# Mind-Synchronizing-Generator.net
KiCad netlist of a schematic drawn in EAGLE
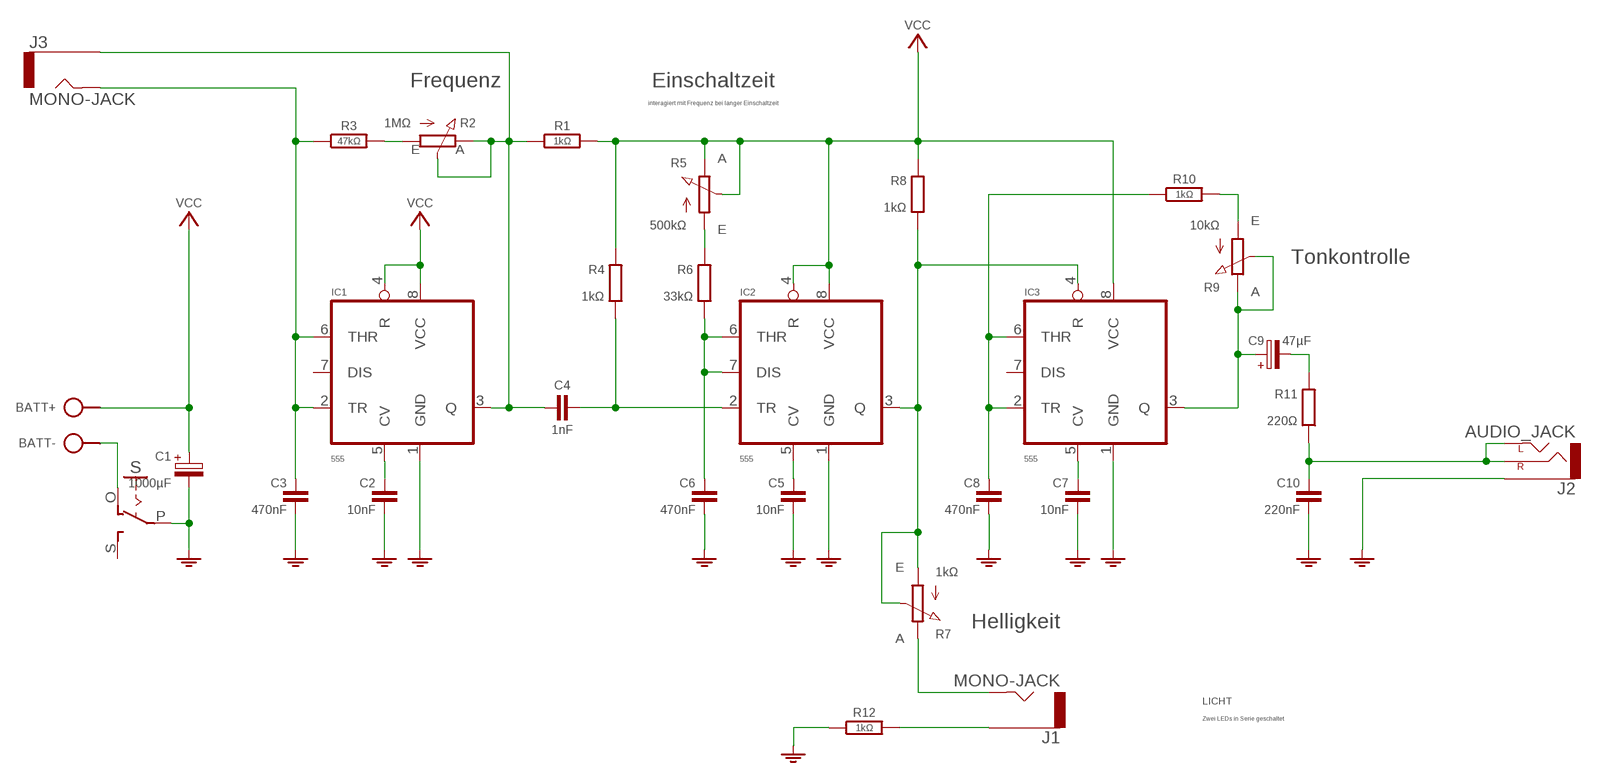
[diagram p0: schematic, sheet 1]

(export (version "E")
  (design (tool "Eeschema 10.0.6"))
  (components
    (comp (ref "BATT")
      (value "SPAD+--+")
      (footprint "eagle-import:SPAD-+")
      (libsource (lib "eagle-import") (part "SPAD+--+"))
    )
    (comp (ref "C1")
      (value "1000µF")
      (footprint "eagle-import:E2,5-6")
      (libsource (lib "eagle-import") (part "CPOLE2.5-6"))
    )
    (comp (ref "C2")
      (value "10nF")
      (footprint "eagle-import:C050-020X044")
      (libsource (lib "eagle-import") (part "C050-020X044"))
    )
    (comp (ref "C3")
      (value "470nF")
      (footprint "eagle-import:C050-040X075")
      (libsource (lib "eagle-import") (part "C050-040X075"))
    )
    (comp (ref "C4")
      (value "1nF")
      (footprint "eagle-import:C050-020X044")
      (libsource (lib "eagle-import") (part "C-H050-020X044"))
    )
    (comp (ref "C5")
      (value "10nF")
      (footprint "eagle-import:C050-020X044_V")
      (libsource (lib "eagle-import") (part "C050-020X044/V"))
    )
    (comp (ref "C6")
      (value "470nF")
      (footprint "eagle-import:C050-040X075")
      (libsource (lib "eagle-import") (part "C050-040X075"))
    )
    (comp (ref "C7")
      (value "10nF")
      (footprint "eagle-import:C075-020X044_V")
      (libsource (lib "eagle-import") (part "C075-020X044/V"))
    )
    (comp (ref "C8")
      (value "470nF")
      (footprint "eagle-import:C050-040X075")
      (libsource (lib "eagle-import") (part "C050-040X075"))
    )
    (comp (ref "C9")
      (value "47µF")
      (footprint "eagle-import:E2,5-4")
      (libsource (lib "eagle-import") (part "CPOL-HE2,5-4"))
    )
    (comp (ref "C10")
      (value "220nF")
      (footprint "eagle-import:C050-025X060")
      (libsource (lib "eagle-import") (part "C025-025X060"))
    )
    (comp (ref "IC1")
      (value "555")
      (footprint "eagle-import:555-DIL")
      (libsource (lib "eagle-import") (part "555_ALT2-LBL"))
    )
    (comp (ref "IC2")
      (value "555")
      (footprint "eagle-import:555-DIL")
      (libsource (lib "eagle-import") (part "555_ALT2-LBL"))
    )
    (comp (ref "IC3")
      (value "555")
      (footprint "eagle-import:555-DIL")
      (libsource (lib "eagle-import") (part "555_ALT2-LBL"))
    )
    (comp (ref "J1")
      (value "MONO-JACK")
      (footprint "eagle-import:STEREOJACK2.5MM_STEREOJACK2.5MM")
      (libsource (lib "eagle-import") (part "MONO-JACK"))
    )
    (comp (ref "J2")
      (value "AUDIO_JACK")
      (footprint "eagle-import:AUDIO-JACK")
      (libsource (lib "eagle-import") (part "AUDIO_JACK"))
    )
    (comp (ref "J3")
      (value "MONO-JACK")
      (footprint "eagle-import:STEREOJACK2.5MM_STEREOJACK2.5MM")
      (libsource (lib "eagle-import") (part "MONO-JACK"))
    )
    (comp (ref "R1")
      (value "1kΩ")
      (footprint "eagle-import:0204_10")
      (libsource (lib "eagle-import") (part "R-H0204/10"))
    )
    (comp (ref "R2")
      (value "1MΩ")
      (footprint "eagle-import:POT-45X40")
      (libsource (lib "eagle-import") (part "POT-H-45X40"))
    )
    (comp (ref "R3")
      (value "47kΩ")
      (footprint "eagle-import:0204_10")
      (libsource (lib "eagle-import") (part "R-H0204/10"))
    )
    (comp (ref "R4")
      (value "1kΩ")
      (footprint "eagle-import:0204_10-V")
      (libsource (lib "eagle-import") (part "R0204/10-V"))
    )
    (comp (ref "R5")
      (value "500kΩ")
      (footprint "eagle-import:POT-45X40")
      (libsource (lib "eagle-import") (part "POT-45X40"))
    )
    (comp (ref "R6")
      (value "33kΩ")
      (footprint "eagle-import:0204_10")
      (libsource (lib "eagle-import") (part "R0204/10"))
    )
    (comp (ref "R7")
      (value "1kΩ")
      (footprint "eagle-import:POT-45X40")
      (libsource (lib "eagle-import") (part "POT-45X40"))
    )
    (comp (ref "R8")
      (value "1kΩ")
      (footprint "eagle-import:0204_10-V")
      (libsource (lib "eagle-import") (part "R0204/10-V"))
    )
    (comp (ref "R9")
      (value "10kΩ")
      (footprint "eagle-import:POT-45X40")
      (libsource (lib "eagle-import") (part "POT-45X40"))
    )
    (comp (ref "R10")
      (value "1kΩ")
      (footprint "eagle-import:0204_10")
      (libsource (lib "eagle-import") (part "R-H0204/10"))
    )
    (comp (ref "R11")
      (value "220Ω")
      (footprint "eagle-import:0204_10-V")
      (libsource (lib "eagle-import") (part "R0204/10-V"))
    )
    (comp (ref "R12")
      (value "1kΩ")
      (footprint "eagle-import:0204_10")
      (libsource (lib "eagle-import") (part "R-H0204/10"))
    )
    (comp (ref "S")
      (value "SL-SW-1P-2T-H")
      (footprint "eagle-import:SLSW-1P2T-H")
      (libsource (lib "eagle-import") (part "SL-SW-1P-2T-H"))
    )
  )
  (nets
    (net (code "1") (name "GND") (class "Default")
      (node (ref "C1") (pin "-") (pinfunction "-_-") (pintype "passive"))
      (node (ref "C10") (pin "2") (pinfunction "2_2") (pintype "passive"))
      (node (ref "C2") (pin "2") (pinfunction "2_2") (pintype "passive"))
      (node (ref "C3") (pin "2") (pinfunction "2_2") (pintype "passive"))
      (node (ref "C5") (pin "2") (pinfunction "2_2") (pintype "passive"))
      (node (ref "C6") (pin "2") (pinfunction "2_2") (pintype "passive"))
      (node (ref "C7") (pin "2") (pinfunction "2_2") (pintype "passive"))
      (node (ref "C8") (pin "2") (pinfunction "2_2") (pintype "passive"))
      (node (ref "IC1") (pin "1") (pinfunction "GND_1") (pintype "power_in"))
      (node (ref "IC2") (pin "1") (pinfunction "GND_1") (pintype "power_in"))
      (node (ref "IC3") (pin "1") (pinfunction "GND_1") (pintype "power_in"))
      (node (ref "J2") (pin "SLEEVE") (pinfunction "SLEEVE_SLEEVE") (pintype "bidirectional"))
      (node (ref "R12") (pin "1") (pinfunction "1_1") (pintype "passive"))
      (node (ref "S") (pin "P") (pinfunction "P_P") (pintype "passive"))
    )
    (net (code "2") (name "Net-(BATTB-P$1)") (class "Default")
      (node (ref "BATT") (pin "1") (pinfunction "P$1_1") (pintype "passive"))
      (node (ref "S") (pin "O") (pinfunction "O_O") (pintype "passive"))
    )
    (net (code "3") (name "Net-(IC1-CV)") (class "Default")
      (node (ref "C2") (pin "1") (pinfunction "1_1") (pintype "passive"))
      (node (ref "IC1") (pin "5") (pinfunction "CV_5") (pintype "input"))
    )
    (net (code "4") (name "Net-(IC1-Q)") (class "Default")
      (node (ref "C4") (pin "1") (pinfunction "1_1") (pintype "passive"))
      (node (ref "IC1") (pin "3") (pinfunction "Q_3") (pintype "output"))
      (node (ref "J3") (pin "SHIELD") (pinfunction "SLEEVE_SHIELD") (pintype "bidirectional"))
      (node (ref "R1") (pin "1") (pinfunction "1_1") (pintype "passive"))
      (node (ref "R2") (pin "E") (pinfunction "E_E") (pintype "passive"))
      (node (ref "R2") (pin "S") (pinfunction "S_S") (pintype "passive"))
    )
    (net (code "5") (name "Net-(IC1-THR)") (class "Default")
      (node (ref "C3") (pin "1") (pinfunction "1_1") (pintype "passive"))
      (node (ref "IC1") (pin "2") (pinfunction "TR_2") (pintype "input"))
      (node (ref "IC1") (pin "6") (pinfunction "THR_6") (pintype "input"))
      (node (ref "J3") (pin "TIP") (pinfunction "LEFT_TIP") (pintype "bidirectional"))
      (node (ref "R3") (pin "1") (pinfunction "1_1") (pintype "passive"))
    )
    (net (code "6") (name "Net-(IC2-CV)") (class "Default")
      (node (ref "C5") (pin "1") (pinfunction "1_1") (pintype "passive"))
      (node (ref "IC2") (pin "5") (pinfunction "CV_5") (pintype "input"))
    )
    (net (code "7") (name "Net-(IC2-DIS)") (class "Default")
      (node (ref "C6") (pin "1") (pinfunction "1_1") (pintype "passive"))
      (node (ref "IC2") (pin "6") (pinfunction "THR_6") (pintype "input"))
      (node (ref "IC2") (pin "7") (pinfunction "DIS_7") (pintype "passive"))
      (node (ref "R6") (pin "2") (pinfunction "1_2") (pintype "passive"))
    )
    (net (code "8") (name "Net-(IC2-Q)") (class "Default")
      (node (ref "IC2") (pin "3") (pinfunction "Q_3") (pintype "output"))
      (node (ref "IC3") (pin "4") (pinfunction "R_4") (pintype "input"))
      (node (ref "R7") (pin "A") (pinfunction "A_A") (pintype "passive"))
      (node (ref "R7") (pin "S") (pinfunction "S_S") (pintype "passive"))
      (node (ref "R8") (pin "2") (pinfunction "1_2") (pintype "passive"))
    )
    (net (code "9") (name "Net-(IC2-TR)") (class "Default")
      (node (ref "C4") (pin "2") (pinfunction "2_2") (pintype "passive"))
      (node (ref "IC2") (pin "2") (pinfunction "TR_2") (pintype "input"))
      (node (ref "R4") (pin "2") (pinfunction "1_2") (pintype "passive"))
    )
    (net (code "10") (name "Net-(IC3-CV)") (class "Default")
      (node (ref "C7") (pin "1") (pinfunction "1_1") (pintype "passive"))
      (node (ref "IC3") (pin "5") (pinfunction "CV_5") (pintype "input"))
    )
    (net (code "11") (name "Net-(IC3-Q)") (class "Default")
      (node (ref "C9") (pin "+") (pinfunction "+_+") (pintype "passive"))
      (node (ref "IC3") (pin "3") (pinfunction "Q_3") (pintype "output"))
      (node (ref "R9") (pin "E") (pinfunction "E_E") (pintype "passive"))
      (node (ref "R9") (pin "S") (pinfunction "S_S") (pintype "passive"))
    )
    (net (code "12") (name "Net-(IC3-THR)") (class "Default")
      (node (ref "C8") (pin "1") (pinfunction "1_1") (pintype "passive"))
      (node (ref "IC3") (pin "2") (pinfunction "TR_2") (pintype "input"))
      (node (ref "IC3") (pin "6") (pinfunction "THR_6") (pintype "input"))
      (node (ref "R10") (pin "1") (pinfunction "1_1") (pintype "passive"))
    )
    (net (code "13") (name "Net-(J1-LEFT)") (class "Default")
      (node (ref "J1") (pin "TIP") (pinfunction "LEFT_TIP") (pintype "bidirectional"))
      (node (ref "R7") (pin "E") (pinfunction "E_E") (pintype "passive"))
    )
    (net (code "14") (name "Net-(J1-SLEEVE)") (class "Default")
      (node (ref "J1") (pin "SHIELD") (pinfunction "SLEEVE_SHIELD") (pintype "bidirectional"))
      (node (ref "R12") (pin "2") (pinfunction "2_2") (pintype "passive"))
    )
    (net (code "15") (name "Net-(J2-LEFT)") (class "Default")
      (node (ref "C10") (pin "1") (pinfunction "1_1") (pintype "passive"))
      (node (ref "J2") (pin "RING") (pinfunction "RIGHT_RING") (pintype "bidirectional"))
      (node (ref "J2") (pin "TIP") (pinfunction "LEFT_TIP") (pintype "bidirectional"))
      (node (ref "R11") (pin "2") (pinfunction "1_2") (pintype "passive"))
    )
    (net (code "16") (name "Net-(R2-PadA)") (class "Default")
      (node (ref "R2") (pin "A") (pinfunction "A_A") (pintype "passive"))
      (node (ref "R3") (pin "2") (pinfunction "2_2") (pintype "passive"))
    )
    (net (code "17") (name "Net-(R6-2)") (class "Default")
      (node (ref "R5") (pin "A") (pinfunction "A_A") (pintype "passive"))
      (node (ref "R6") (pin "1") (pinfunction "2_1") (pintype "passive"))
    )
    (net (code "18") (name "Net-(R10-Pad2)") (class "Default")
      (node (ref "R10") (pin "2") (pinfunction "2_2") (pintype "passive"))
      (node (ref "R9") (pin "A") (pinfunction "A_A") (pintype "passive"))
    )
    (net (code "19") (name "Net-(R11-2)") (class "Default")
      (node (ref "C9") (pin "-") (pinfunction "-_-") (pintype "passive"))
      (node (ref "R11") (pin "1") (pinfunction "2_1") (pintype "passive"))
    )
    (net (code "20") (name "VCC") (class "Default")
      (node (ref "BATT") (pin "2") (pinfunction "P$1_2") (pintype "passive"))
      (node (ref "C1") (pin "+") (pinfunction "+_+") (pintype "passive"))
      (node (ref "IC1") (pin "4") (pinfunction "R_4") (pintype "input"))
      (node (ref "IC1") (pin "8") (pinfunction "VCC_8") (pintype "power_in"))
      (node (ref "IC2") (pin "4") (pinfunction "R_4") (pintype "input"))
      (node (ref "IC2") (pin "8") (pinfunction "VCC_8") (pintype "power_in"))
      (node (ref "IC3") (pin "8") (pinfunction "VCC_8") (pintype "power_in"))
      (node (ref "R1") (pin "2") (pinfunction "2_2") (pintype "passive"))
      (node (ref "R4") (pin "1") (pinfunction "2_1") (pintype "passive"))
      (node (ref "R5") (pin "E") (pinfunction "E_E") (pintype "passive"))
      (node (ref "R5") (pin "S") (pinfunction "S_S") (pintype "passive"))
      (node (ref "R8") (pin "1") (pinfunction "2_1") (pintype "passive"))
    )
    (net (code "21") (name "unconnected-(IC1-DIS-Pad7)") (class "Default")
      (node (ref "IC1") (pin "7") (pinfunction "DIS_7") (pintype "passive"))
    )
    (net (code "22") (name "unconnected-(IC3-DIS-Pad7)") (class "Default")
      (node (ref "IC3") (pin "7") (pinfunction "DIS_7") (pintype "passive"))
    )
    (net (code "23") (name "unconnected-(S-PadS)") (class "Default")
      (node (ref "S") (pin "S") (pinfunction "S_S") (pintype "passive"))
    )
  )
)
